# AUDIO_2.net
KiCad netlist of a schematic drawn in Altium Designer
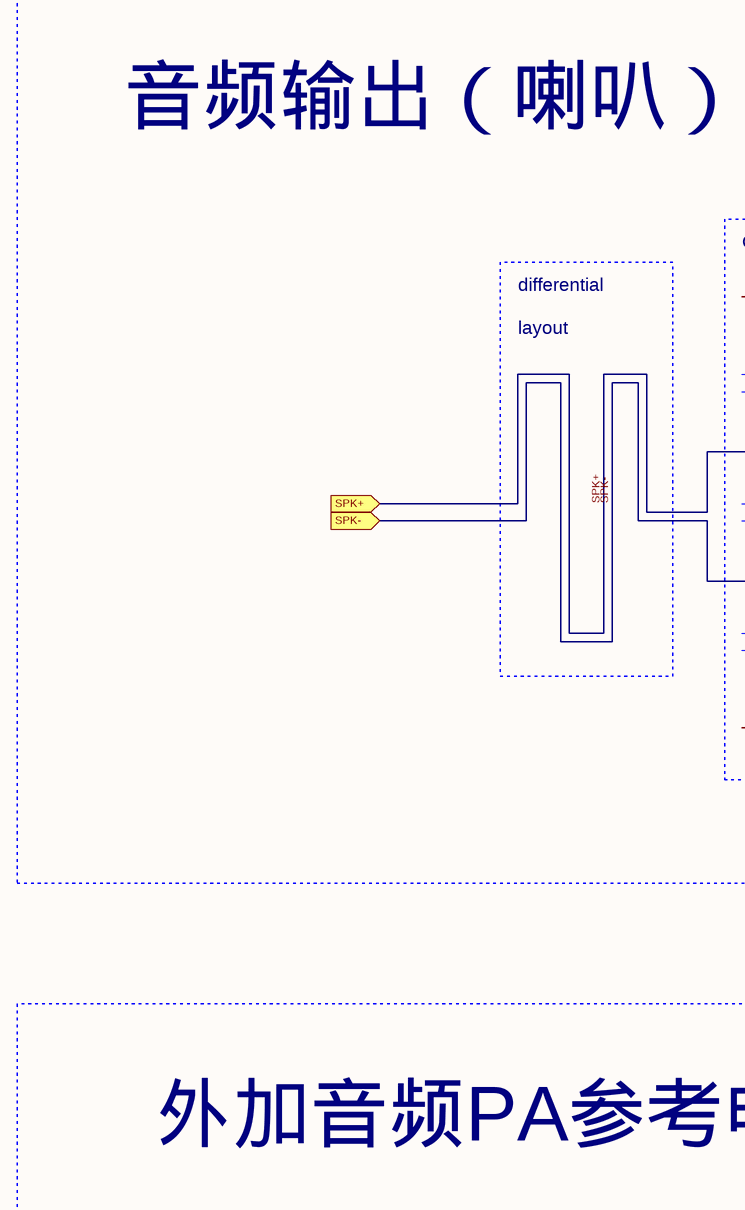
[diagram p0: AUDIO_2.SchDoc, top left]
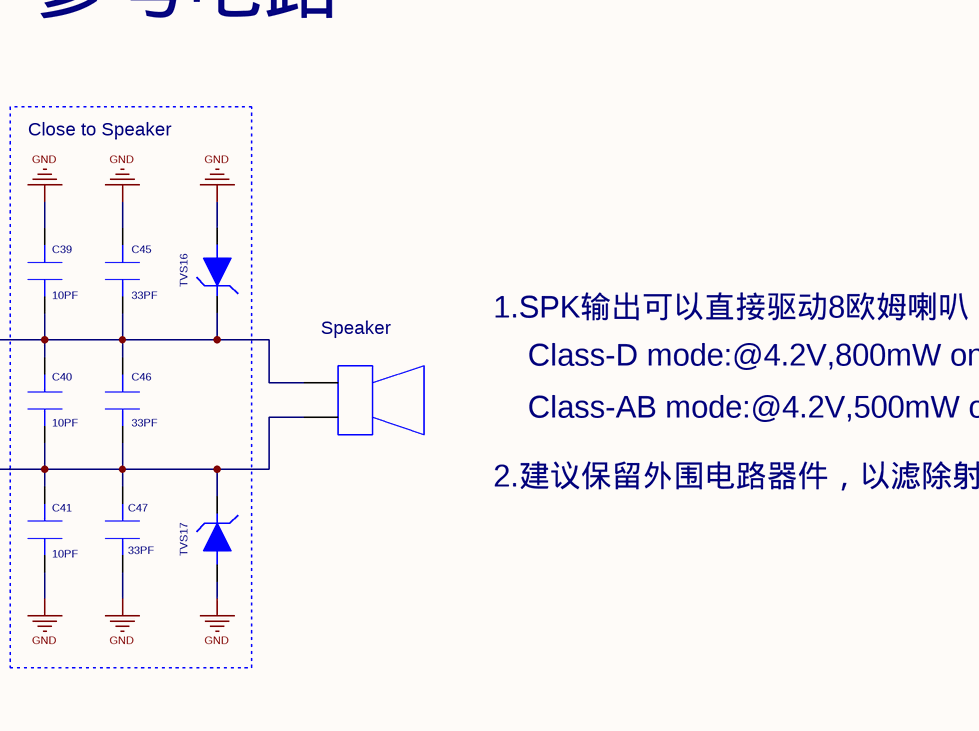
[diagram p1: AUDIO_2.SchDoc, top middle]
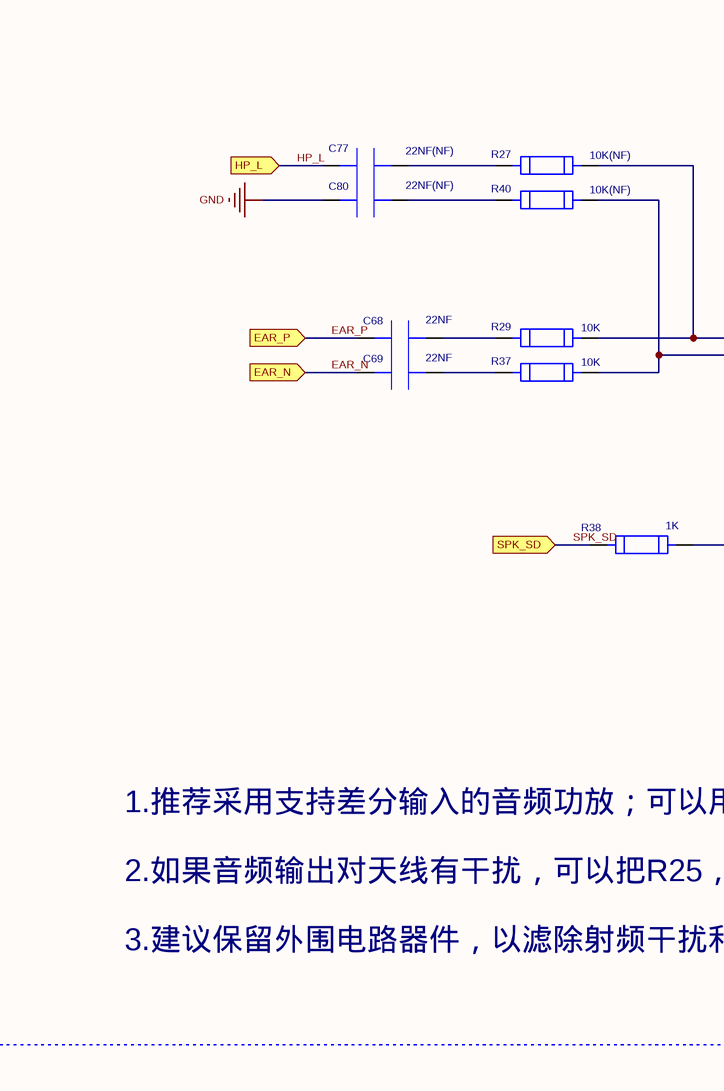
[diagram p2: AUDIO_2.SchDoc, bottom left]
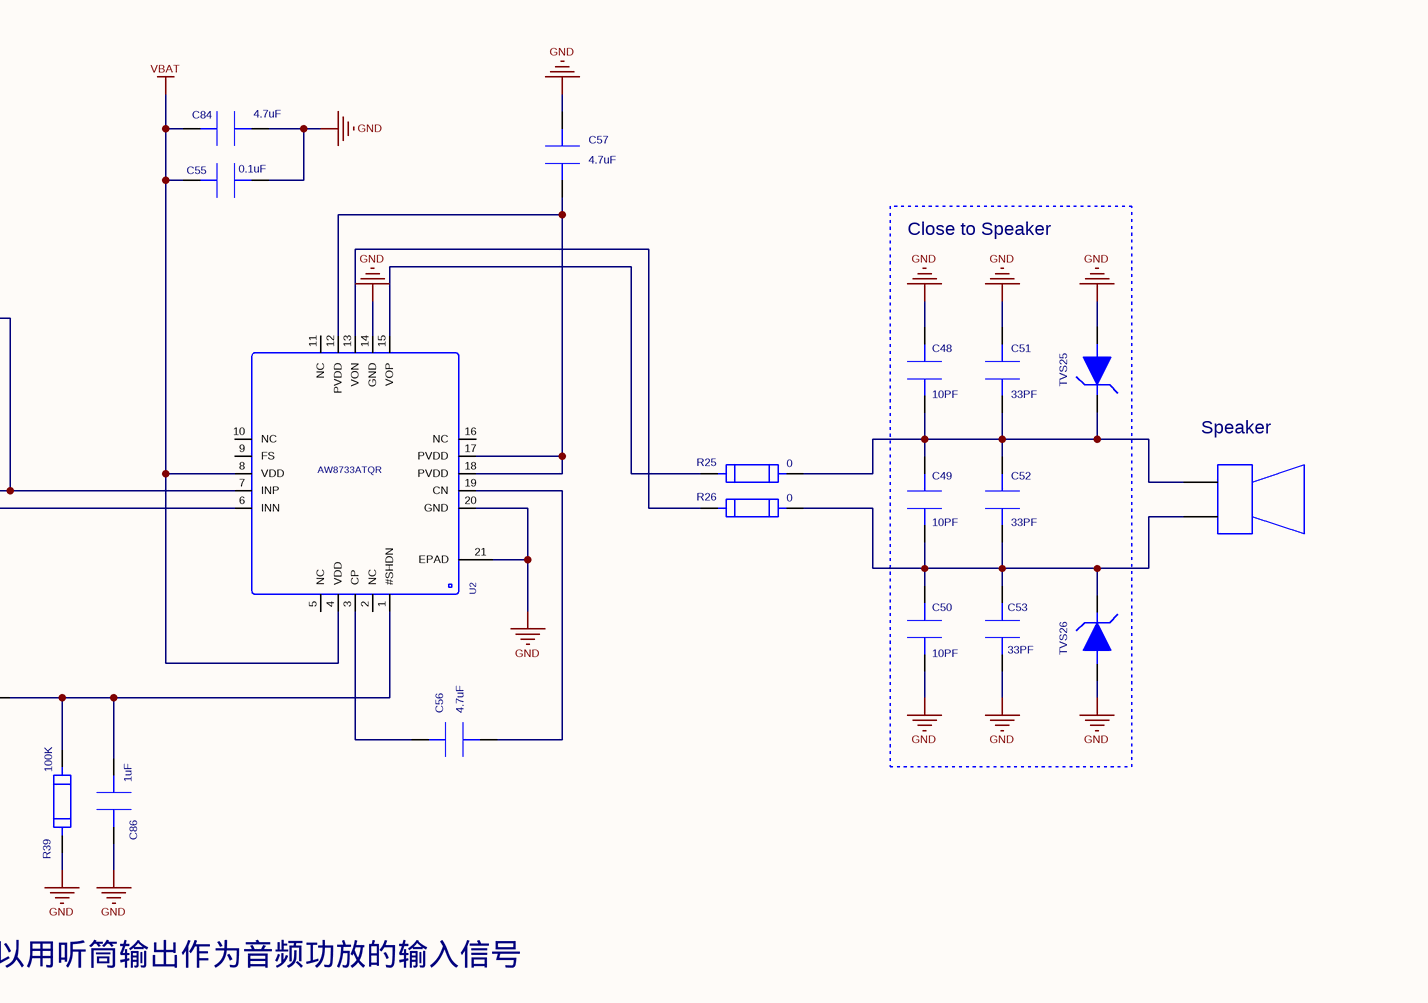
[diagram p3: AUDIO_2.SchDoc, bottom middle]
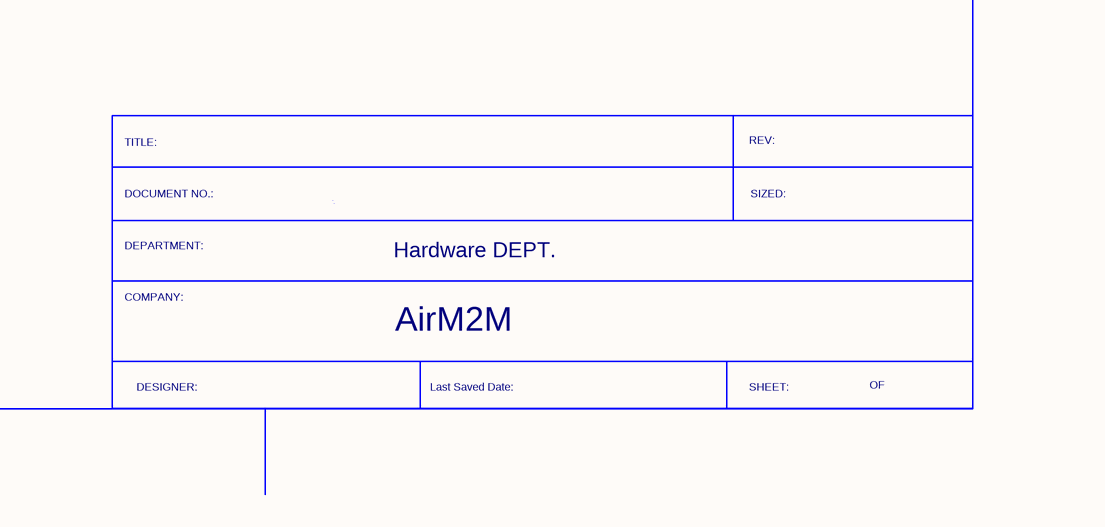
[diagram p4: AUDIO_2.SchDoc, bottom right]

(export (version "E")
  (design (tool "Eeschema 10.0.6"))
  (components
    (comp (ref "C39")
      (value "10PF")
      (footprint "SC0201")
      (description "CAP CER C0G;10PF;+/-5%;25V;0201;0.35mm;ROHS")
      (fields (field (name "TOLERANCE") "+/-5%") (field (name "Comment") "CAP-10PF-0201-COG"))
      (libsource (lib "*") (part "CAP-10PF-0201-COG"))
    )
    (comp (ref "C40")
      (value "10PF")
      (footprint "SC0201")
      (description "CAP CER C0G;10PF;+/-5%;25V;0201;0.35mm;ROHS")
      (fields (field (name "TOLERANCE") "+/-5%") (field (name "Comment") "CAP-10PF-0201-COG"))
      (libsource (lib "*") (part "CAP-10PF-0201-COG"))
    )
    (comp (ref "C41")
      (value "10PF")
      (footprint "SC0201")
      (description "CAP CER C0G;10PF;+/-5%;25V;0201;0.35mm;ROHS")
      (fields (field (name "TOLERANCE") "+/-5%") (field (name "Comment") "CAP-10PF-0201-COG"))
      (libsource (lib "*") (part "CAP-10PF-0201-COG"))
    )
    (comp (ref "C45")
      (value "33PF")
      (footprint "SC0201")
      (description "CAP CER C0G;10PF;+/-5%;25V;0201;0.35mm;ROHS")
      (fields (field (name "TOLERANCE") "+/-5%") (field (name "Comment") "CAP-10PF-0201-COG"))
      (libsource (lib "*") (part "CAP-10PF-0201-COG"))
    )
    (comp (ref "C46")
      (value "33PF")
      (footprint "SC0201")
      (description "CAP CER C0G;10PF;+/-5%;25V;0201;0.35mm;ROHS")
      (fields (field (name "TOLERANCE") "+/-5%") (field (name "Comment") "CAP-10PF-0201-COG"))
      (libsource (lib "*") (part "CAP-10PF-0201-COG"))
    )
    (comp (ref "C47")
      (value "33PF")
      (footprint "SC0201")
      (description "CAP CER C0G;10PF;+/-5%;25V;0201;0.35mm;ROHS")
      (fields (field (name "TOLERANCE") "+/-5%") (field (name "Comment") "CAP-10PF-0201-COG"))
      (libsource (lib "*") (part "CAP-10PF-0201-COG"))
    )
    (comp (ref "C48")
      (value "10PF")
      (footprint "SC0201")
      (description "CAP CER C0G;10PF;+/-5%;25V;0201;0.35mm;ROHS")
      (fields (field (name "TOLERANCE") "+/-5%") (field (name "Comment") "CAP-10PF-0201-COG"))
      (libsource (lib "*") (part "CAP-10PF-0201-COG"))
    )
    (comp (ref "C49")
      (value "10PF")
      (footprint "SC0201")
      (description "CAP CER C0G;10PF;+/-5%;25V;0201;0.35mm;ROHS")
      (fields (field (name "TOLERANCE") "+/-5%") (field (name "Comment") "CAP-10PF-0201-COG"))
      (libsource (lib "*") (part "CAP-10PF-0201-COG"))
    )
    (comp (ref "C50")
      (value "10PF")
      (footprint "SC0201")
      (description "CAP CER C0G;10PF;+/-5%;25V;0201;0.35mm;ROHS")
      (fields (field (name "TOLERANCE") "+/-5%") (field (name "Comment") "CAP-10PF-0201-COG"))
      (libsource (lib "*") (part "CAP-10PF-0201-COG"))
    )
    (comp (ref "C51")
      (value "33PF")
      (footprint "SC0201")
      (description "CAP CER C0G;10PF;+/-5%;25V;0201;0.35mm;ROHS")
      (fields (field (name "TOLERANCE") "+/-5%") (field (name "Comment") "CAP-10PF-0201-COG"))
      (libsource (lib "*") (part "CAP-10PF-0201-COG"))
    )
    (comp (ref "C52")
      (value "33PF")
      (footprint "SC0201")
      (description "CAP CER C0G;10PF;+/-5%;25V;0201;0.35mm;ROHS")
      (fields (field (name "TOLERANCE") "+/-5%") (field (name "Comment") "CAP-10PF-0201-COG"))
      (libsource (lib "*") (part "CAP-10PF-0201-COG"))
    )
    (comp (ref "C53")
      (value "33PF")
      (footprint "SC0201")
      (description "CAP CER C0G;10PF;+/-5%;25V;0201;0.35mm;ROHS")
      (fields (field (name "TOLERANCE") "+/-5%") (field (name "Comment") "CAP-10PF-0201-COG"))
      (libsource (lib "*") (part "CAP-10PF-0201-COG"))
    )
    (comp (ref "C55")
      (value "0.1uF")
      (footprint "SC0402")
      (description "CAP CER X5R/X7R;0.1uF;+/-10%;10V;0402;0.5mm;ROHS")
      (fields (field (name "TOLERANCE") "+/-10%") (field (name "Comment") "CAP-0.1UF-0402-X5R-10V"))
      (libsource (lib "*") (part "CAP-0.1UF-0402-X5R-10V"))
    )
    (comp (ref "C56")
      (value "4.7uF")
      (footprint "SC0603")
      (description "CAP CER Y5V;4.7uF;+80% -20%;10V;0603;0.8mm;ROHS")
      (fields (field (name "TOLERANCE") "+/-10%") (field (name "Comment") "CAP-4.7UF-0603-Y5V-10V"))
      (libsource (lib "*") (part "CAP-4.7UF-0603-Y5V-10V"))
    )
    (comp (ref "C57")
      (value "4.7uF")
      (footprint "SC0603")
      (description "CAP CER Y5V;4.7uF;+80% -20%;10V;0603;0.8mm;ROHS")
      (fields (field (name "TOLERANCE") "+/-10%") (field (name "Comment") "CAP-4.7UF-0603-Y5V-10V"))
      (libsource (lib "*") (part "CAP-4.7UF-0603-Y5V-10V"))
    )
    (comp (ref "C68")
      (value "22NF")
      (footprint "SC0402")
      (description "CAP CER X7R;22NF;+/-10%;50V;0402;0.5mm;ROHS")
      (fields (field (name "TOLERANCE") "+/-10%") (field (name "Comment") "CAP-22NF-0402-X7R"))
      (libsource (lib "*") (part "CAP-22NF-0402-X7R"))
    )
    (comp (ref "C69")
      (value "22NF")
      (footprint "SC0402")
      (description "CAP CER X7R;22NF;+/-10%;50V;0402;0.5mm;ROHS")
      (fields (field (name "TOLERANCE") "+/-10%") (field (name "Comment") "CAP-22NF-0402-X7R"))
      (libsource (lib "*") (part "CAP-22NF-0402-X7R"))
    )
    (comp (ref "C77")
      (value "22NF(NF)")
      (footprint "SC0402")
      (description "CAP CER X7R;22NF;+/-10%;50V;0402;0.5mm;ROHS")
      (fields (field (name "TOLERANCE") "+/-10%") (field (name "Comment") "CAP-22NF-0402-X7R"))
      (libsource (lib "*") (part "CAP-22NF-0402-X7R"))
    )
    (comp (ref "C80")
      (value "22NF(NF)")
      (footprint "SC0402")
      (description "CAP CER X7R;22NF;+/-10%;50V;0402;0.5mm;ROHS")
      (fields (field (name "TOLERANCE") "+/-10%") (field (name "Comment") "CAP-22NF-0402-X7R"))
      (libsource (lib "*") (part "CAP-22NF-0402-X7R"))
    )
    (comp (ref "C84")
      (value "4.7uF")
      (footprint "SC0603")
      (description "CAP CER Y5V;4.7uF;+80% -20%;10V;0603;0.8mm;ROHS")
      (fields (field (name "TOLERANCE") "+/-10%") (field (name "Comment") "CAP-4.7UF-0603-Y5V-10V"))
      (libsource (lib "*") (part "CAP-4.7UF-0603-Y5V-10V"))
    )
    (comp (ref "C86")
      (value "1uF")
      (footprint "SC0402")
      (description "CAP CER X5R;1uF;+/-10%;6.3V;0402;0.5mm;ROHS")
      (fields (field (name "TOLERANCE") "+/-10%") (field (name "Comment") "CAP-1UF-0402-X5R"))
      (libsource (lib "*") (part "CAP-1UF-0402-X5R"))
    )
    (comp (ref "J8")
      (value "AUDIO-SPEAKER-BLUEHY")
      (footprint "CON2-2")
      (libsource (lib "*") (part "AUDIO-SPEAKER-BLUEHY"))
    )
    (comp (ref "J9")
      (value "AUDIO-SPEAKER-BLUEHY")
      (footprint "CON2-2")
      (libsource (lib "*") (part "AUDIO-SPEAKER-BLUEHY"))
    )
    (comp (ref "R25")
      (value "0")
      (footprint "SR0402")
      (description "RES FILM;0;1A;0402;0.4mm;ROHS")
      (fields (field (name "Comment") "RES-0-0402"))
      (libsource (lib "*") (part "RES-0-0402"))
    )
    (comp (ref "R26")
      (value "0")
      (footprint "SR0402")
      (description "RES FILM;0;1A;0402;0.4mm;ROHS")
      (fields (field (name "Comment") "RES-0-0402"))
      (libsource (lib "*") (part "RES-0-0402"))
    )
    (comp (ref "R27")
      (value "10K(NF)")
      (footprint "SR0402")
      (description "RES FILM;10K;+/-1%;1/16W;0402;0.4mm;ROHS")
      (fields (field (name "TOLERANCE") "+/-1%") (field (name "Comment") "RES-10K-+-1%-0402"))
      (libsource (lib "*") (part "RES-10K-+-1%-0402"))
    )
    (comp (ref "R29")
      (value "10K")
      (footprint "SR0402")
      (description "RES FILM;10K;+/-1%;1/16W;0402;0.4mm;ROHS")
      (fields (field (name "TOLERANCE") "+/-1%") (field (name "Comment") "RES-10K-+-1%-0402"))
      (libsource (lib "*") (part "RES-10K-+-1%-0402"))
    )
    (comp (ref "R37")
      (value "10K")
      (footprint "SR0402")
      (description "RES FILM;10K;+/-1%;1/16W;0402;0.4mm;ROHS")
      (fields (field (name "TOLERANCE") "+/-1%") (field (name "Comment") "RES-10K-+-1%-0402"))
      (libsource (lib "*") (part "RES-10K-+-1%-0402"))
    )
    (comp (ref "R38")
      (value "1K")
      (footprint "SR0402")
      (description "RES FILM;1K;+/-5%;1/16W;0402;0.4mm;ROHS")
      (fields (field (name "TOLERANCE") "+/-5%") (field (name "Comment") "RES-1K-0402"))
      (libsource (lib "*") (part "RES-1K-0402"))
    )
    (comp (ref "R39")
      (value "100K")
      (footprint "SR0402")
      (description "RES FILM;100K;+/-5%;1/16W;0402;0.4mm;ROHS")
      (fields (field (name "TOLERANCE") "+/-5%") (field (name "Comment") "RES-100K-0402"))
      (libsource (lib "*") (part "RES-100K-0402"))
    )
    (comp (ref "R40")
      (value "10K(NF)")
      (footprint "SR0402")
      (description "RES FILM;10K;+/-1%;1/16W;0402;0.4mm;ROHS")
      (fields (field (name "TOLERANCE") "+/-1%") (field (name "Comment") "RES-10K-+-1%-0402"))
      (libsource (lib "*") (part "RES-10K-+-1%-0402"))
    )
    (comp (ref "TVS16")
      (value "ESD-TVS-ESD9X5.0ST5G")
      (footprint "SOD-923-ESD9X5.0ST5G")
      (description "TVS;5.0V;65PF;SOD?923;ROHS")
      (libsource (lib "*") (part "ESD-TVS-ESD9X5.0ST5G"))
    )
    (comp (ref "TVS17")
      (value "ESD-TVS-ESD9X5.0ST5G")
      (footprint "SOD-923-ESD9X5.0ST5G")
      (description "TVS;5.0V;65PF;SOD?923;ROHS")
      (libsource (lib "*") (part "ESD-TVS-ESD9X5.0ST5G"))
    )
    (comp (ref "TVS25")
      (value "ESD-TVS-ESD9X5.0ST5G")
      (footprint "SOD-923-ESD9X5.0ST5G")
      (description "TVS;5.0V;65PF;SOD?923;ROHS")
      (libsource (lib "*") (part "ESD-TVS-ESD9X5.0ST5G"))
    )
    (comp (ref "TVS26")
      (value "ESD-TVS-ESD9X5.0ST5G")
      (footprint "SOD-923-ESD9X5.0ST5G")
      (description "TVS;5.0V;65PF;SOD?923;ROHS")
      (libsource (lib "*") (part "ESD-TVS-ESD9X5.0ST5G"))
    )
    (comp (ref "U2")
      (value "AW8733ATQR")
      (footprint "TQFN-20L_L3.0-W3.0-P0.40-BL-EP")
      (fields (field (name "BOM_SUPPLIER_PART") "C139593") (field (name "CONTRIBUTOR") "LCSC"))
      (libsource (lib "*") (part "AW8733ATQR"))
    )
  )
  (nets
    (net (code "1") (name "/EAR_N") (class "Default")
      (node (ref "C69") (pin "1") (pinfunction "1_1") (pintype "passive"))
    )
    (net (code "2") (name "/EAR_P") (class "Default")
      (node (ref "C68") (pin "1") (pinfunction "1_1") (pintype "passive"))
    )
    (net (code "3") (name "/HP_L") (class "Default")
      (node (ref "C77") (pin "1") (pinfunction "1_1") (pintype "passive"))
    )
    (net (code "4") (name "/SPK+") (class "Default")
      (node (ref "C39") (pin "2") (pinfunction "2_2") (pintype "passive"))
      (node (ref "C40") (pin "1") (pinfunction "1_1") (pintype "passive"))
      (node (ref "C45") (pin "2") (pinfunction "2_2") (pintype "passive"))
      (node (ref "C46") (pin "1") (pinfunction "1_1") (pintype "passive"))
      (node (ref "J8") (pin "1") (pinfunction "1_1") (pintype "passive"))
      (node (ref "TVS16") (pin "1") (pinfunction "1_1") (pintype "passive"))
    )
    (net (code "5") (name "/SPK-") (class "Default")
      (node (ref "C40") (pin "2") (pinfunction "2_2") (pintype "passive"))
      (node (ref "C41") (pin "1") (pinfunction "1_1") (pintype "passive"))
      (node (ref "C46") (pin "2") (pinfunction "2_2") (pintype "passive"))
      (node (ref "C47") (pin "1") (pinfunction "1_1") (pintype "passive"))
      (node (ref "J8") (pin "2") (pinfunction "2_2") (pintype "passive"))
      (node (ref "TVS17") (pin "1") (pinfunction "1_1") (pintype "passive"))
    )
    (net (code "6") (name "/SPK_SD") (class "Default")
      (node (ref "R38") (pin "1") (pinfunction "1_1") (pintype "passive"))
    )
    (net (code "7") (name "GND") (class "Default")
      (node (ref "C39") (pin "1") (pinfunction "1_1") (pintype "passive"))
      (node (ref "C41") (pin "2") (pinfunction "2_2") (pintype "passive"))
      (node (ref "C45") (pin "1") (pinfunction "1_1") (pintype "passive"))
      (node (ref "C47") (pin "2") (pinfunction "2_2") (pintype "passive"))
      (node (ref "C48") (pin "1") (pinfunction "1_1") (pintype "passive"))
      (node (ref "C50") (pin "2") (pinfunction "2_2") (pintype "passive"))
      (node (ref "C51") (pin "1") (pinfunction "1_1") (pintype "passive"))
      (node (ref "C53") (pin "2") (pinfunction "2_2") (pintype "passive"))
      (node (ref "C55") (pin "1") (pinfunction "1_1") (pintype "passive"))
      (node (ref "C57") (pin "1") (pinfunction "1_1") (pintype "passive"))
      (node (ref "C80") (pin "1") (pinfunction "1_1") (pintype "passive"))
      (node (ref "C84") (pin "2") (pinfunction "2_2") (pintype "passive"))
      (node (ref "C86") (pin "1") (pinfunction "1_1") (pintype "passive"))
      (node (ref "R39") (pin "1") (pinfunction "1_1") (pintype "passive"))
      (node (ref "TVS16") (pin "2") (pinfunction "2_2") (pintype "passive"))
      (node (ref "TVS17") (pin "2") (pinfunction "2_2") (pintype "passive"))
      (node (ref "TVS25") (pin "2") (pinfunction "2_2") (pintype "passive"))
      (node (ref "TVS26") (pin "2") (pinfunction "2_2") (pintype "passive"))
      (node (ref "U2") (pin "14") (pinfunction "GND_14") (pintype "passive"))
      (node (ref "U2") (pin "20") (pinfunction "GND_20") (pintype "passive"))
      (node (ref "U2") (pin "21") (pinfunction "EPAD_21") (pintype "passive"))
    )
    (net (code "8") (name "Net-(C48-Pad2)") (class "Default")
      (node (ref "C48") (pin "2") (pinfunction "2_2") (pintype "passive"))
      (node (ref "C49") (pin "1") (pinfunction "1_1") (pintype "passive"))
      (node (ref "C51") (pin "2") (pinfunction "2_2") (pintype "passive"))
      (node (ref "C52") (pin "1") (pinfunction "1_1") (pintype "passive"))
      (node (ref "J9") (pin "1") (pinfunction "1_1") (pintype "passive"))
      (node (ref "R25") (pin "2") (pinfunction "2_2") (pintype "passive"))
      (node (ref "TVS25") (pin "1") (pinfunction "1_1") (pintype "passive"))
    )
    (net (code "9") (name "Net-(C49-Pad2)") (class "Default")
      (node (ref "C49") (pin "2") (pinfunction "2_2") (pintype "passive"))
      (node (ref "C50") (pin "1") (pinfunction "1_1") (pintype "passive"))
      (node (ref "C52") (pin "2") (pinfunction "2_2") (pintype "passive"))
      (node (ref "C53") (pin "1") (pinfunction "1_1") (pintype "passive"))
      (node (ref "J9") (pin "2") (pinfunction "2_2") (pintype "passive"))
      (node (ref "R26") (pin "2") (pinfunction "2_2") (pintype "passive"))
      (node (ref "TVS26") (pin "1") (pinfunction "1_1") (pintype "passive"))
    )
    (net (code "10") (name "Net-(C57-Pad2)") (class "Default")
      (node (ref "C57") (pin "2") (pinfunction "2_2") (pintype "passive"))
      (node (ref "U2") (pin "12") (pinfunction "PVDD_12") (pintype "passive"))
      (node (ref "U2") (pin "17") (pinfunction "PVDD_17") (pintype "passive"))
      (node (ref "U2") (pin "18") (pinfunction "PVDD_18") (pintype "passive"))
    )
    (net (code "11") (name "Net-(C68-Pad2)") (class "Default")
      (node (ref "C68") (pin "2") (pinfunction "2_2") (pintype "passive"))
      (node (ref "R29") (pin "1") (pinfunction "1_1") (pintype "passive"))
    )
    (net (code "12") (name "Net-(C69-Pad2)") (class "Default")
      (node (ref "C69") (pin "2") (pinfunction "2_2") (pintype "passive"))
      (node (ref "R37") (pin "1") (pinfunction "1_1") (pintype "passive"))
    )
    (net (code "13") (name "Net-(C77-Pad2)") (class "Default")
      (node (ref "C77") (pin "2") (pinfunction "2_2") (pintype "passive"))
      (node (ref "R27") (pin "1") (pinfunction "1_1") (pintype "passive"))
    )
    (net (code "14") (name "Net-(C80-Pad2)") (class "Default")
      (node (ref "C80") (pin "2") (pinfunction "2_2") (pintype "passive"))
      (node (ref "R40") (pin "1") (pinfunction "1_1") (pintype "passive"))
    )
    (net (code "15") (name "Net-(U2-#SHDN)") (class "Default")
      (node (ref "C86") (pin "2") (pinfunction "2_2") (pintype "passive"))
      (node (ref "R38") (pin "2") (pinfunction "2_2") (pintype "passive"))
      (node (ref "R39") (pin "2") (pinfunction "2_2") (pintype "passive"))
      (node (ref "U2") (pin "1") (pinfunction "#SHDN_1") (pintype "passive"))
    )
    (net (code "16") (name "Net-(U2-CN)") (class "Default")
      (node (ref "C56") (pin "2") (pinfunction "2_2") (pintype "passive"))
      (node (ref "U2") (pin "19") (pinfunction "CN_19") (pintype "passive"))
    )
    (net (code "17") (name "Net-(U2-CP)") (class "Default")
      (node (ref "C56") (pin "1") (pinfunction "1_1") (pintype "passive"))
      (node (ref "U2") (pin "3") (pinfunction "CP_3") (pintype "passive"))
    )
    (net (code "18") (name "Net-(U2-INN)") (class "Default")
      (node (ref "R37") (pin "2") (pinfunction "2_2") (pintype "passive"))
      (node (ref "R40") (pin "2") (pinfunction "2_2") (pintype "passive"))
      (node (ref "U2") (pin "6") (pinfunction "INN_6") (pintype "passive"))
    )
    (net (code "19") (name "Net-(U2-INP)") (class "Default")
      (node (ref "R27") (pin "2") (pinfunction "2_2") (pintype "passive"))
      (node (ref "R29") (pin "2") (pinfunction "2_2") (pintype "passive"))
      (node (ref "U2") (pin "7") (pinfunction "INP_7") (pintype "passive"))
    )
    (net (code "20") (name "Net-(U2-VON)") (class "Default")
      (node (ref "R26") (pin "1") (pinfunction "1_1") (pintype "passive"))
      (node (ref "U2") (pin "13") (pinfunction "VON_13") (pintype "passive"))
    )
    (net (code "21") (name "Net-(U2-VOP)") (class "Default")
      (node (ref "R25") (pin "1") (pinfunction "1_1") (pintype "passive"))
      (node (ref "U2") (pin "15") (pinfunction "VOP_15") (pintype "passive"))
    )
    (net (code "22") (name "VBAT") (class "Default")
      (node (ref "C55") (pin "2") (pinfunction "2_2") (pintype "passive"))
      (node (ref "C84") (pin "1") (pinfunction "1_1") (pintype "passive"))
      (node (ref "U2") (pin "4") (pinfunction "VDD_4") (pintype "passive"))
      (node (ref "U2") (pin "8") (pinfunction "VDD_8") (pintype "passive"))
    )
    (net (code "23") (name "unconnected-(U2-FS-Pad9)") (class "Default")
      (node (ref "U2") (pin "9") (pinfunction "FS_9") (pintype "passive"))
    )
    (net (code "24") (name "unconnected-(U2-NC-Pad2)") (class "Default")
      (node (ref "U2") (pin "2") (pinfunction "NC_2") (pintype "passive"))
    )
    (net (code "25") (name "unconnected-(U2-NC-Pad5)") (class "Default")
      (node (ref "U2") (pin "5") (pinfunction "NC_5") (pintype "passive"))
    )
    (net (code "26") (name "unconnected-(U2-NC-Pad10)") (class "Default")
      (node (ref "U2") (pin "10") (pinfunction "NC_10") (pintype "passive"))
    )
    (net (code "27") (name "unconnected-(U2-NC-Pad11)") (class "Default")
      (node (ref "U2") (pin "11") (pinfunction "NC_11") (pintype "passive"))
    )
    (net (code "28") (name "unconnected-(U2-NC-Pad16)") (class "Default")
      (node (ref "U2") (pin "16") (pinfunction "NC_16") (pintype "passive"))
    )
  )
)
